# Arduio_matrix-shield_02.net
KiCad netlist of a schematic drawn in EAGLE
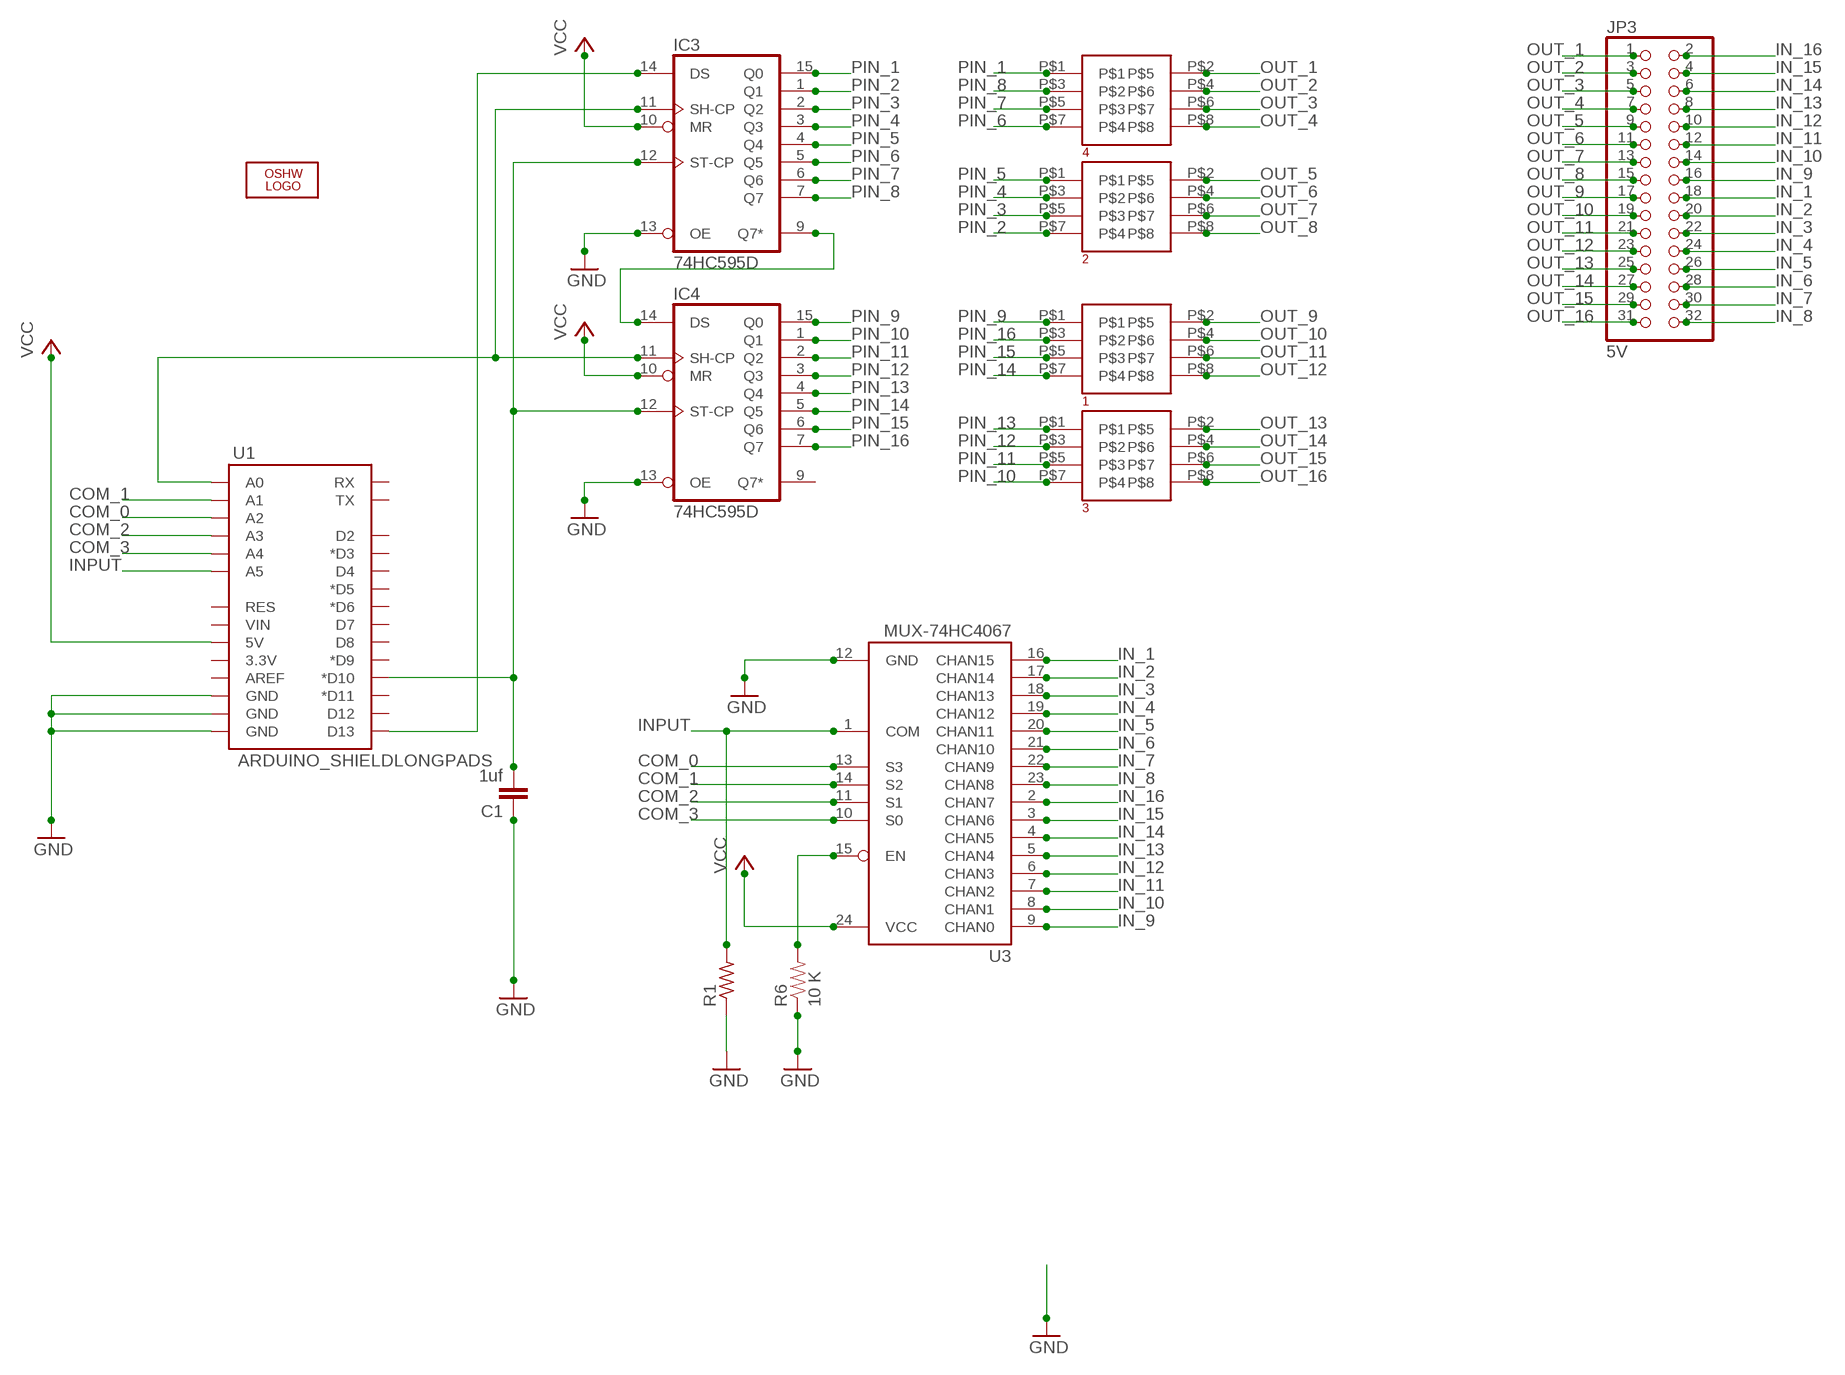
[diagram p0: schematic, sheet 1]

(export (version "E")
  (design (tool "Eeschema 10.0.6"))
  (components
    (comp (ref "1")
      (value "D83A")
      (footprint "eagle-import:D83A")
      (libsource (lib "eagle-import") (part "D83A"))
    )
    (comp (ref "2")
      (value "D83A")
      (footprint "eagle-import:D83A")
      (libsource (lib "eagle-import") (part "D83A"))
    )
    (comp (ref "3")
      (value "D83A")
      (footprint "eagle-import:D83A")
      (libsource (lib "eagle-import") (part "D83A"))
    )
    (comp (ref "4")
      (value "D83A")
      (footprint "eagle-import:D83A")
      (libsource (lib "eagle-import") (part "D83A"))
    )
    (comp (ref "C1")
      (value "1uf")
      (footprint "eagle-import:1206")
      (libsource (lib "eagle-import") (part "2.2UF-CERCAP-10009"))
    )
    (comp (ref "IC3")
      (value "74HC595D")
      (footprint "eagle-import:SO16")
      (libsource (lib "eagle-import") (part "74595DHC"))
    )
    (comp (ref "IC4")
      (value "74HC595D")
      (footprint "eagle-import:SO16")
      (libsource (lib "eagle-import") (part "74595DHC"))
    )
    (comp (ref "JP3")
      (value "5V")
      (footprint "eagle-import:2X16_90")
      (libsource (lib "eagle-import") (part "PINHD-2X16/90"))
    )
    (comp (ref "OSHW")
      (value "OSHW_LOGO_8MILX0350-NT")
      (footprint "eagle-import:OSHW_8X350_NOTEXT")
      (libsource (lib "eagle-import") (part "OSHW_LOGO_8MILX0350-NT"))
    )
    (comp (ref "R1")
      (value "R-US_0204/7")
      (footprint "eagle-import:0204_7")
      (libsource (lib "eagle-import") (part "R-US_0204/7"))
    )
    (comp (ref "R6")
      (value "10 K")
      (footprint "eagle-import:1206")
      (libsource (lib "eagle-import") (part "RESISTOR1206"))
    )
    (comp (ref "U1")
      (value "ARDUINO_SHIELDLONGPADS")
      (footprint "eagle-import:DUEMILANOVE_SHIELD_LONGPADS")
      (libsource (lib "eagle-import") (part "ARDUINO_SHIELDLONGPADS"))
    )
    (comp (ref "U3")
      (value "MUX-74HC4067")
      (footprint "eagle-import:SSOP24")
      (libsource (lib "eagle-import") (part "MUX-74HC4067SMD"))
    )
  )
  (nets
    (net (code "1") (name "/COM_0") (class "Default")
      (node (ref "U1") (pin "A2") (pinfunction "A2_A2") (pintype "bidirectional"))
      (node (ref "U3") (pin "13") (pinfunction "S3_13") (pintype "input"))
    )
    (net (code "2") (name "/COM_1") (class "Default")
      (node (ref "U1") (pin "A1") (pinfunction "A1_A1") (pintype "bidirectional"))
      (node (ref "U3") (pin "14") (pinfunction "S2_14") (pintype "input"))
    )
    (net (code "3") (name "/COM_2") (class "Default")
      (node (ref "U1") (pin "A3") (pinfunction "A3_A3") (pintype "bidirectional"))
      (node (ref "U3") (pin "11") (pinfunction "S1_11") (pintype "input"))
    )
    (net (code "4") (name "/COM_3") (class "Default")
      (node (ref "U1") (pin "A4") (pinfunction "A4_A4") (pintype "bidirectional"))
      (node (ref "U3") (pin "10") (pinfunction "S0_10") (pintype "input"))
    )
    (net (code "5") (name "/INPUT") (class "Default")
      (node (ref "R1") (pin "2") (pinfunction "2_2") (pintype "passive"))
      (node (ref "U1") (pin "A5") (pinfunction "A5_A5") (pintype "bidirectional"))
      (node (ref "U3") (pin "1") (pinfunction "COM_1") (pintype "bidirectional"))
    )
    (net (code "6") (name "/IN_1") (class "Default")
      (node (ref "JP3") (pin "18") (pinfunction "18_18") (pintype "passive"))
      (node (ref "U3") (pin "16") (pinfunction "CHAN15_16") (pintype "bidirectional"))
    )
    (net (code "7") (name "/IN_2") (class "Default")
      (node (ref "JP3") (pin "20") (pinfunction "20_20") (pintype "passive"))
      (node (ref "U3") (pin "17") (pinfunction "CHAN14_17") (pintype "bidirectional"))
    )
    (net (code "8") (name "/IN_3") (class "Default")
      (node (ref "JP3") (pin "22") (pinfunction "22_22") (pintype "passive"))
      (node (ref "U3") (pin "18") (pinfunction "CHAN13_18") (pintype "bidirectional"))
    )
    (net (code "9") (name "/IN_4") (class "Default")
      (node (ref "JP3") (pin "24") (pinfunction "24_24") (pintype "passive"))
      (node (ref "U3") (pin "19") (pinfunction "CHAN12_19") (pintype "bidirectional"))
    )
    (net (code "10") (name "/IN_5") (class "Default")
      (node (ref "JP3") (pin "26") (pinfunction "26_26") (pintype "passive"))
      (node (ref "U3") (pin "20") (pinfunction "CHAN11_20") (pintype "bidirectional"))
    )
    (net (code "11") (name "/IN_6") (class "Default")
      (node (ref "JP3") (pin "28") (pinfunction "28_28") (pintype "passive"))
      (node (ref "U3") (pin "21") (pinfunction "CHAN10_21") (pintype "bidirectional"))
    )
    (net (code "12") (name "/IN_7") (class "Default")
      (node (ref "JP3") (pin "30") (pinfunction "30_30") (pintype "passive"))
      (node (ref "U3") (pin "22") (pinfunction "CHAN9_22") (pintype "bidirectional"))
    )
    (net (code "13") (name "/IN_8") (class "Default")
      (node (ref "JP3") (pin "32") (pinfunction "32_32") (pintype "passive"))
      (node (ref "U3") (pin "23") (pinfunction "CHAN8_23") (pintype "bidirectional"))
    )
    (net (code "14") (name "/IN_9") (class "Default")
      (node (ref "JP3") (pin "16") (pinfunction "16_16") (pintype "passive"))
      (node (ref "U3") (pin "9") (pinfunction "CHAN0_9") (pintype "bidirectional"))
    )
    (net (code "15") (name "/IN_10") (class "Default")
      (node (ref "JP3") (pin "14") (pinfunction "14_14") (pintype "passive"))
      (node (ref "U3") (pin "8") (pinfunction "CHAN1_8") (pintype "bidirectional"))
    )
    (net (code "16") (name "/IN_11") (class "Default")
      (node (ref "JP3") (pin "12") (pinfunction "12_12") (pintype "passive"))
      (node (ref "U3") (pin "7") (pinfunction "CHAN2_7") (pintype "bidirectional"))
    )
    (net (code "17") (name "/IN_12") (class "Default")
      (node (ref "JP3") (pin "10") (pinfunction "10_10") (pintype "passive"))
      (node (ref "U3") (pin "6") (pinfunction "CHAN3_6") (pintype "bidirectional"))
    )
    (net (code "18") (name "/IN_13") (class "Default")
      (node (ref "JP3") (pin "8") (pinfunction "8_8") (pintype "passive"))
      (node (ref "U3") (pin "5") (pinfunction "CHAN4_5") (pintype "bidirectional"))
    )
    (net (code "19") (name "/IN_14") (class "Default")
      (node (ref "JP3") (pin "6") (pinfunction "6_6") (pintype "passive"))
      (node (ref "U3") (pin "4") (pinfunction "CHAN5_4") (pintype "bidirectional"))
    )
    (net (code "20") (name "/IN_15") (class "Default")
      (node (ref "JP3") (pin "4") (pinfunction "4_4") (pintype "passive"))
      (node (ref "U3") (pin "3") (pinfunction "CHAN6_3") (pintype "bidirectional"))
    )
    (net (code "21") (name "/IN_16") (class "Default")
      (node (ref "JP3") (pin "2") (pinfunction "2_2") (pintype "passive"))
      (node (ref "U3") (pin "2") (pinfunction "CHAN7_2") (pintype "bidirectional"))
    )
    (net (code "22") (name "/OUT_1") (class "Default")
      (node (ref "4") (pin "P$2") (pinfunction "P$5_P$2") (pintype "bidirectional"))
      (node (ref "JP3") (pin "1") (pinfunction "1_1") (pintype "passive"))
    )
    (net (code "23") (name "/OUT_2") (class "Default")
      (node (ref "4") (pin "P$4") (pinfunction "P$6_P$4") (pintype "bidirectional"))
      (node (ref "JP3") (pin "3") (pinfunction "3_3") (pintype "passive"))
    )
    (net (code "24") (name "/OUT_3") (class "Default")
      (node (ref "4") (pin "P$6") (pinfunction "P$7_P$6") (pintype "bidirectional"))
      (node (ref "JP3") (pin "5") (pinfunction "5_5") (pintype "passive"))
    )
    (net (code "25") (name "/OUT_4") (class "Default")
      (node (ref "4") (pin "P$8") (pinfunction "P$8_P$8") (pintype "bidirectional"))
      (node (ref "JP3") (pin "7") (pinfunction "7_7") (pintype "passive"))
    )
    (net (code "26") (name "/OUT_5") (class "Default")
      (node (ref "2") (pin "P$2") (pinfunction "P$5_P$2") (pintype "bidirectional"))
      (node (ref "JP3") (pin "9") (pinfunction "9_9") (pintype "passive"))
    )
    (net (code "27") (name "/OUT_6") (class "Default")
      (node (ref "2") (pin "P$4") (pinfunction "P$6_P$4") (pintype "bidirectional"))
      (node (ref "JP3") (pin "11") (pinfunction "11_11") (pintype "passive"))
    )
    (net (code "28") (name "/OUT_7") (class "Default")
      (node (ref "2") (pin "P$6") (pinfunction "P$7_P$6") (pintype "bidirectional"))
      (node (ref "JP3") (pin "13") (pinfunction "13_13") (pintype "passive"))
    )
    (net (code "29") (name "/OUT_8") (class "Default")
      (node (ref "2") (pin "P$8") (pinfunction "P$8_P$8") (pintype "bidirectional"))
      (node (ref "JP3") (pin "15") (pinfunction "15_15") (pintype "passive"))
    )
    (net (code "30") (name "/OUT_9") (class "Default")
      (node (ref "1") (pin "P$2") (pinfunction "P$5_P$2") (pintype "bidirectional"))
      (node (ref "JP3") (pin "17") (pinfunction "17_17") (pintype "passive"))
    )
    (net (code "31") (name "/OUT_10") (class "Default")
      (node (ref "1") (pin "P$4") (pinfunction "P$6_P$4") (pintype "bidirectional"))
      (node (ref "JP3") (pin "19") (pinfunction "19_19") (pintype "passive"))
    )
    (net (code "32") (name "/OUT_11") (class "Default")
      (node (ref "1") (pin "P$6") (pinfunction "P$7_P$6") (pintype "bidirectional"))
      (node (ref "JP3") (pin "21") (pinfunction "21_21") (pintype "passive"))
    )
    (net (code "33") (name "/OUT_12") (class "Default")
      (node (ref "1") (pin "P$8") (pinfunction "P$8_P$8") (pintype "bidirectional"))
      (node (ref "JP3") (pin "23") (pinfunction "23_23") (pintype "passive"))
    )
    (net (code "34") (name "/OUT_13") (class "Default")
      (node (ref "3") (pin "P$2") (pinfunction "P$5_P$2") (pintype "bidirectional"))
      (node (ref "JP3") (pin "25") (pinfunction "25_25") (pintype "passive"))
    )
    (net (code "35") (name "/OUT_14") (class "Default")
      (node (ref "3") (pin "P$4") (pinfunction "P$6_P$4") (pintype "bidirectional"))
      (node (ref "JP3") (pin "27") (pinfunction "27_27") (pintype "passive"))
    )
    (net (code "36") (name "/OUT_15") (class "Default")
      (node (ref "3") (pin "P$6") (pinfunction "P$7_P$6") (pintype "bidirectional"))
      (node (ref "JP3") (pin "29") (pinfunction "29_29") (pintype "passive"))
    )
    (net (code "37") (name "/OUT_16") (class "Default")
      (node (ref "3") (pin "P$8") (pinfunction "P$8_P$8") (pintype "bidirectional"))
      (node (ref "JP3") (pin "31") (pinfunction "31_31") (pintype "passive"))
    )
    (net (code "38") (name "/PIN_1") (class "Default")
      (node (ref "4") (pin "P$1") (pinfunction "P$1_P$1") (pintype "bidirectional"))
      (node (ref "IC3") (pin "15") (pinfunction "Q0_15") (pintype "tri_state"))
    )
    (net (code "39") (name "/PIN_2") (class "Default")
      (node (ref "2") (pin "P$7") (pinfunction "P$4_P$7") (pintype "bidirectional"))
      (node (ref "IC3") (pin "1") (pinfunction "Q1_1") (pintype "tri_state"))
    )
    (net (code "40") (name "/PIN_3") (class "Default")
      (node (ref "2") (pin "P$5") (pinfunction "P$3_P$5") (pintype "bidirectional"))
      (node (ref "IC3") (pin "2") (pinfunction "Q2_2") (pintype "tri_state"))
    )
    (net (code "41") (name "/PIN_4") (class "Default")
      (node (ref "2") (pin "P$3") (pinfunction "P$2_P$3") (pintype "bidirectional"))
      (node (ref "IC3") (pin "3") (pinfunction "Q3_3") (pintype "tri_state"))
    )
    (net (code "42") (name "/PIN_5") (class "Default")
      (node (ref "2") (pin "P$1") (pinfunction "P$1_P$1") (pintype "bidirectional"))
      (node (ref "IC3") (pin "4") (pinfunction "Q4_4") (pintype "tri_state"))
    )
    (net (code "43") (name "/PIN_6") (class "Default")
      (node (ref "4") (pin "P$7") (pinfunction "P$4_P$7") (pintype "bidirectional"))
      (node (ref "IC3") (pin "5") (pinfunction "Q5_5") (pintype "tri_state"))
    )
    (net (code "44") (name "/PIN_7") (class "Default")
      (node (ref "4") (pin "P$5") (pinfunction "P$3_P$5") (pintype "bidirectional"))
      (node (ref "IC3") (pin "6") (pinfunction "Q6_6") (pintype "tri_state"))
    )
    (net (code "45") (name "/PIN_8") (class "Default")
      (node (ref "4") (pin "P$3") (pinfunction "P$2_P$3") (pintype "bidirectional"))
      (node (ref "IC3") (pin "7") (pinfunction "Q7_7") (pintype "tri_state"))
    )
    (net (code "46") (name "/PIN_9") (class "Default")
      (node (ref "1") (pin "P$1") (pinfunction "P$1_P$1") (pintype "bidirectional"))
      (node (ref "IC4") (pin "15") (pinfunction "Q0_15") (pintype "tri_state"))
    )
    (net (code "47") (name "/PIN_10") (class "Default")
      (node (ref "3") (pin "P$7") (pinfunction "P$4_P$7") (pintype "bidirectional"))
      (node (ref "IC4") (pin "1") (pinfunction "Q1_1") (pintype "tri_state"))
    )
    (net (code "48") (name "/PIN_11") (class "Default")
      (node (ref "3") (pin "P$5") (pinfunction "P$3_P$5") (pintype "bidirectional"))
      (node (ref "IC4") (pin "2") (pinfunction "Q2_2") (pintype "tri_state"))
    )
    (net (code "49") (name "/PIN_12") (class "Default")
      (node (ref "3") (pin "P$3") (pinfunction "P$2_P$3") (pintype "bidirectional"))
      (node (ref "IC4") (pin "3") (pinfunction "Q3_3") (pintype "tri_state"))
    )
    (net (code "50") (name "/PIN_13") (class "Default")
      (node (ref "3") (pin "P$1") (pinfunction "P$1_P$1") (pintype "bidirectional"))
      (node (ref "IC4") (pin "4") (pinfunction "Q4_4") (pintype "tri_state"))
    )
    (net (code "51") (name "/PIN_14") (class "Default")
      (node (ref "1") (pin "P$7") (pinfunction "P$4_P$7") (pintype "bidirectional"))
      (node (ref "IC4") (pin "5") (pinfunction "Q5_5") (pintype "tri_state"))
    )
    (net (code "52") (name "/PIN_15") (class "Default")
      (node (ref "1") (pin "P$5") (pinfunction "P$3_P$5") (pintype "bidirectional"))
      (node (ref "IC4") (pin "6") (pinfunction "Q6_6") (pintype "tri_state"))
    )
    (net (code "53") (name "/PIN_16") (class "Default")
      (node (ref "1") (pin "P$3") (pinfunction "P$2_P$3") (pintype "bidirectional"))
      (node (ref "IC4") (pin "7") (pinfunction "Q7_7") (pintype "tri_state"))
    )
    (net (code "54") (name "GND") (class "Default")
      (node (ref "C1") (pin "1") (pinfunction "1_1") (pintype "passive"))
      (node (ref "IC3") (pin "13") (pinfunction "OE_13") (pintype "input"))
      (node (ref "IC4") (pin "13") (pinfunction "OE_13") (pintype "input"))
      (node (ref "R1") (pin "1") (pinfunction "1_1") (pintype "passive"))
      (node (ref "R6") (pin "1") (pinfunction "1_1") (pintype "passive"))
      (node (ref "U1") (pin "GND@0") (pinfunction "GND_GND@0") (pintype "bidirectional"))
      (node (ref "U1") (pin "GND@1") (pinfunction "GND_GND@1") (pintype "bidirectional"))
      (node (ref "U1") (pin "GND@2") (pinfunction "GND_GND@2") (pintype "bidirectional"))
      (node (ref "U3") (pin "12") (pinfunction "GND_12") (pintype "bidirectional"))
    )
    (net (code "55") (name "Net-(IC3A-DS)") (class "Default")
      (node (ref "IC3") (pin "14") (pinfunction "DS_14") (pintype "input"))
      (node (ref "U1") (pin "D13") (pinfunction "D13_D13") (pintype "bidirectional"))
    )
    (net (code "56") (name "Net-(IC3A-Q7*)") (class "Default")
      (node (ref "IC3") (pin "9") (pinfunction "Q7*_9") (pintype "tri_state"))
      (node (ref "IC4") (pin "14") (pinfunction "DS_14") (pintype "input"))
    )
    (net (code "57") (name "Net-(IC3A-SH-CP)") (class "Default")
      (node (ref "IC3") (pin "11") (pinfunction "SH-CP_11") (pintype "input"))
      (node (ref "IC4") (pin "11") (pinfunction "SH-CP_11") (pintype "input"))
      (node (ref "U1") (pin "A0") (pinfunction "A0_A0") (pintype "bidirectional"))
    )
    (net (code "58") (name "Net-(IC3A-ST-CP)") (class "Default")
      (node (ref "C1") (pin "2") (pinfunction "2_2") (pintype "passive"))
      (node (ref "IC3") (pin "12") (pinfunction "ST-CP_12") (pintype "input"))
      (node (ref "IC4") (pin "12") (pinfunction "ST-CP_12") (pintype "input"))
      (node (ref "U1") (pin "D10") (pinfunction "*D10_D10") (pintype "bidirectional"))
    )
    (net (code "59") (name "Net-(U3-EN)") (class "Default")
      (node (ref "R6") (pin "2") (pinfunction "2_2") (pintype "passive"))
      (node (ref "U3") (pin "15") (pinfunction "EN_15") (pintype "input"))
    )
    (net (code "60") (name "VCC") (class "Default")
      (node (ref "IC3") (pin "10") (pinfunction "MR_10") (pintype "input"))
      (node (ref "IC4") (pin "10") (pinfunction "MR_10") (pintype "input"))
      (node (ref "U1") (pin "5V") (pinfunction "5V_5V") (pintype "bidirectional"))
      (node (ref "U3") (pin "24") (pinfunction "VCC_24") (pintype "bidirectional"))
    )
    (net (code "61") (name "unconnected-(IC4A-Q7*-Pad9)") (class "Default")
      (node (ref "IC4") (pin "9") (pinfunction "Q7*_9") (pintype "tri_state"))
    )
    (net (code "62") (name "unconnected-(U1-*D3-PadD3)") (class "Default")
      (node (ref "U1") (pin "D3") (pinfunction "*D3_D3") (pintype "bidirectional"))
    )
    (net (code "63") (name "unconnected-(U1-*D5-PadD5)") (class "Default")
      (node (ref "U1") (pin "D5") (pinfunction "*D5_D5") (pintype "bidirectional"))
    )
    (net (code "64") (name "unconnected-(U1-*D6-PadD6)") (class "Default")
      (node (ref "U1") (pin "D6") (pinfunction "*D6_D6") (pintype "bidirectional"))
    )
    (net (code "65") (name "unconnected-(U1-*D9-PadD9)") (class "Default")
      (node (ref "U1") (pin "D9") (pinfunction "*D9_D9") (pintype "bidirectional"))
    )
    (net (code "66") (name "unconnected-(U1-*D11-PadD11)") (class "Default")
      (node (ref "U1") (pin "D11") (pinfunction "*D11_D11") (pintype "bidirectional"))
    )
    (net (code "67") (name "unconnected-(U1-Pad3.3V)") (class "Default")
      (node (ref "U1") (pin "3.3V") (pinfunction "3.3V_3.3V") (pintype "bidirectional"))
    )
    (net (code "68") (name "unconnected-(U1-PadAREF)") (class "Default")
      (node (ref "U1") (pin "AREF") (pinfunction "AREF_AREF") (pintype "bidirectional"))
    )
    (net (code "69") (name "unconnected-(U1-PadD2)") (class "Default")
      (node (ref "U1") (pin "D2") (pinfunction "D2_D2") (pintype "bidirectional"))
    )
    (net (code "70") (name "unconnected-(U1-PadD4)") (class "Default")
      (node (ref "U1") (pin "D4") (pinfunction "D4_D4") (pintype "bidirectional"))
    )
    (net (code "71") (name "unconnected-(U1-PadD7)") (class "Default")
      (node (ref "U1") (pin "D7") (pinfunction "D7_D7") (pintype "bidirectional"))
    )
    (net (code "72") (name "unconnected-(U1-PadD8)") (class "Default")
      (node (ref "U1") (pin "D8") (pinfunction "D8_D8") (pintype "bidirectional"))
    )
    (net (code "73") (name "unconnected-(U1-PadD12)") (class "Default")
      (node (ref "U1") (pin "D12") (pinfunction "D12_D12") (pintype "bidirectional"))
    )
    (net (code "74") (name "unconnected-(U1-PadRES)") (class "Default")
      (node (ref "U1") (pin "RES") (pinfunction "RES_RES") (pintype "bidirectional"))
    )
    (net (code "75") (name "unconnected-(U1-PadRX)") (class "Default")
      (node (ref "U1") (pin "RX") (pinfunction "RX_RX") (pintype "bidirectional"))
    )
    (net (code "76") (name "unconnected-(U1-PadTX)") (class "Default")
      (node (ref "U1") (pin "TX") (pinfunction "TX_TX") (pintype "bidirectional"))
    )
    (net (code "77") (name "unconnected-(U1-PadVIN)") (class "Default")
      (node (ref "U1") (pin "VIN") (pinfunction "VIN_VIN") (pintype "bidirectional"))
    )
  )
)
